# Menu-Control-Motor.net
KiCad netlist of a schematic drawn in Altium Designer
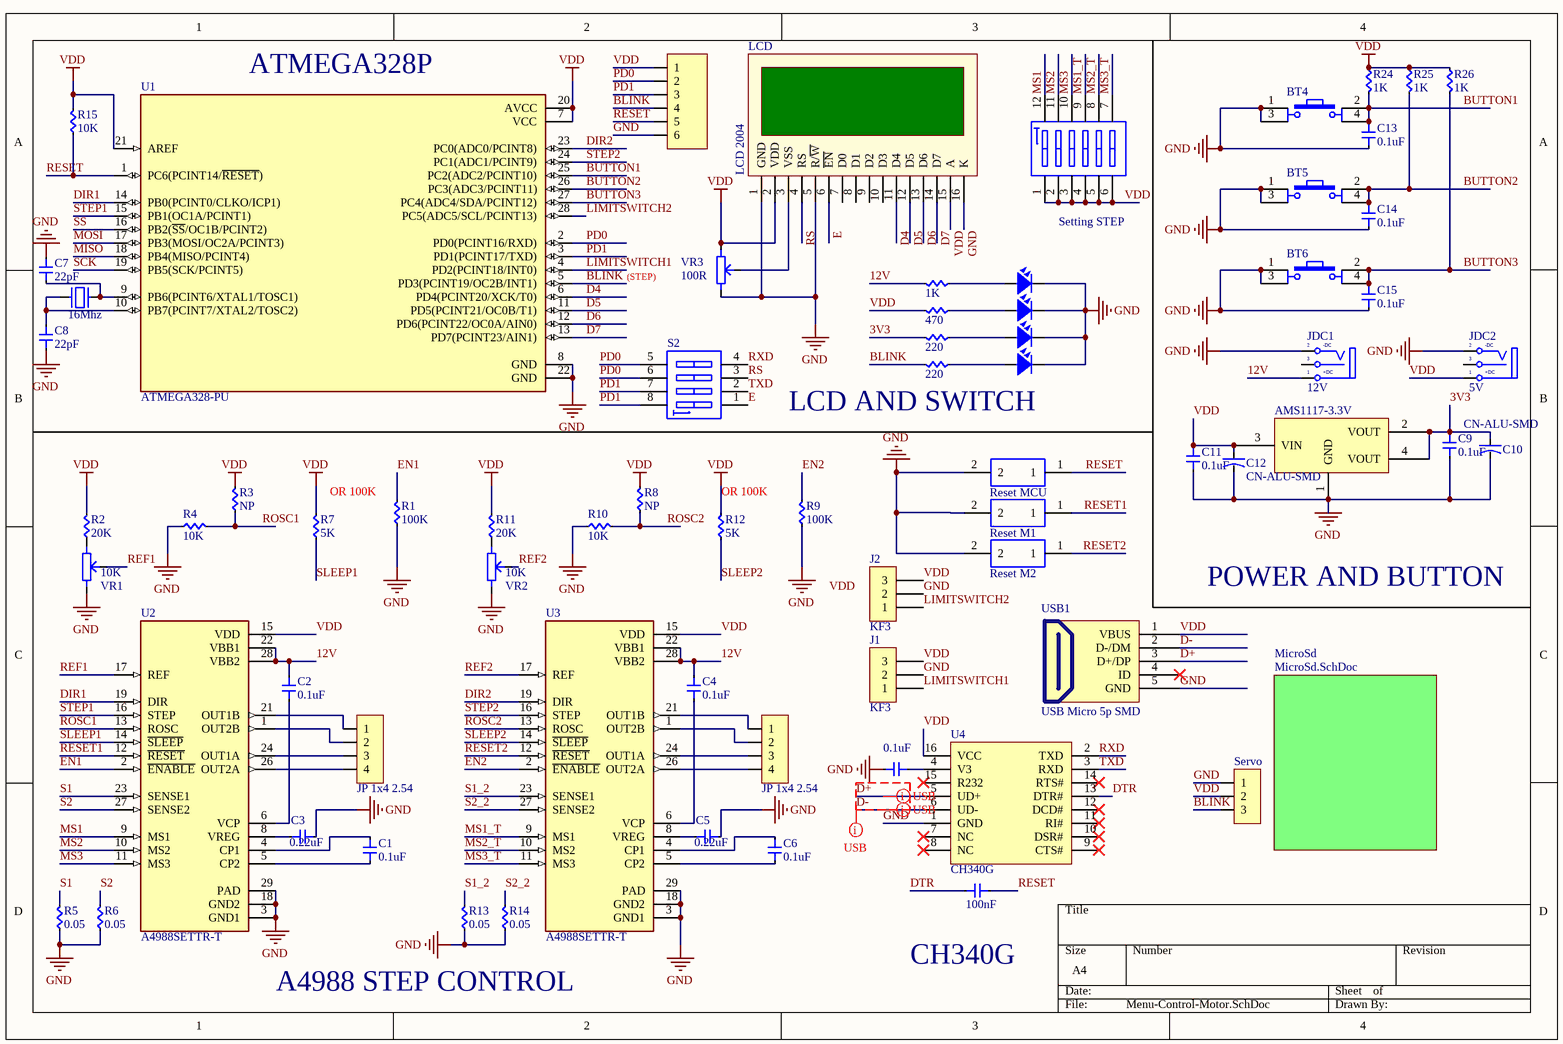
[diagram p0: Menu-Control-Motor.SchDoc]

(export (version "E")
  (design (tool "Eeschema 10.0.6"))
  (components
    (comp (ref "AMS1117-3.3V")
      (value "AMS1117-3.3V")
      (footprint "SOT223")
      (description "Dán")
      (libsource (lib "Altium_Lib_by_KhueNguyenCreator") (part "AMS1117 SMD"))
    )
    (comp (ref "BT4")
      (value "Button 4p")
      (footprint "SMD button 4 pins 6x6")
      (libsource (lib "CMN") (part "Button 4p"))
    )
    (comp (ref "BT5")
      (value "Button 4p")
      (footprint "SMD button 4 pins 6x6")
      (libsource (lib "CMN") (part "Button 4p"))
    )
    (comp (ref "BT6")
      (value "Button 4p")
      (footprint "SMD button 4 pins 6x6")
      (libsource (lib "CMN") (part "Button 4p"))
    )
    (comp (ref "C1")
      (value "0.1uF")
      (footprint "Cap 0805")
      (description "Capacitor SMD 0805")
      (libsource (lib "Altium_Lib_by_KhueNguyenCreator") (part "Cap 0805"))
    )
    (comp (ref "C2")
      (value "0.1uF")
      (footprint "Cap 0805")
      (description "Capacitor SMD 0805")
      (libsource (lib "Altium_Lib_by_KhueNguyenCreator") (part "Cap 0805"))
    )
    (comp (ref "C3")
      (value "0.22uF")
      (footprint "Cap 0805")
      (description "Capacitor SMD 0805")
      (libsource (lib "Altium_Lib_by_KhueNguyenCreator") (part "Cap 0805"))
    )
    (comp (ref "C4")
      (value "0.1uF")
      (footprint "Cap 0805")
      (description "Capacitor SMD 0805")
      (libsource (lib "Altium_Lib_by_KhueNguyenCreator") (part "Cap 0805"))
    )
    (comp (ref "C5")
      (value "0.22uF")
      (footprint "Cap 0805")
      (description "Capacitor SMD 0805")
      (libsource (lib "Altium_Lib_by_KhueNguyenCreator") (part "Cap 0805"))
    )
    (comp (ref "C6")
      (value "0.1uF")
      (footprint "Cap 0805")
      (description "Capacitor SMD 0805")
      (libsource (lib "Altium_Lib_by_KhueNguyenCreator") (part "Cap 0805"))
    )
    (comp (ref "C7")
      (value "22pF")
      (footprint "Cap 0805")
      (description "Capacitor SMD 0805")
      (libsource (lib "Altium_Lib_by_KhueNguyenCreator") (part "Cap 0805"))
    )
    (comp (ref "C8")
      (value "22pF")
      (footprint "Cap 0805")
      (description "Capacitor SMD 0805")
      (libsource (lib "Altium_Lib_by_KhueNguyenCreator") (part "Cap 0805"))
    )
    (comp (ref "C9")
      (value "0.1uF")
      (footprint "Cap 0805")
      (description "Capacitor SMD 0805")
      (libsource (lib "Altium_Lib_by_KhueNguyenCreator") (part "Cap 0805"))
    )
    (comp (ref "C10")
      (value "CN-ALU-SMD")
      (footprint "CAP-ALU-SMD-6.3x7.7x2.2")
      (description "Polarized Capacitor (Axial)")
      (fields (field (name "PUBLISHER") "Altium Limited"))
      (libsource (lib "LIBRARY") (part "CN-ALU-SMD"))
    )
    (comp (ref "C11")
      (value "0.1uF")
      (footprint "Cap 0805")
      (description "Capacitor SMD 0805")
      (libsource (lib "Altium_Lib_by_KhueNguyenCreator") (part "Cap 0805"))
    )
    (comp (ref "C12")
      (value "CN-ALU-SMD")
      (footprint "CAP-ALU-SMD-6.3x7.7x2.2")
      (description "Polarized Capacitor (Axial)")
      (fields (field (name "PUBLISHER") "Altium Limited"))
      (libsource (lib "LIBRARY") (part "CN-ALU-SMD"))
    )
    (comp (ref "C13")
      (value "0.1uF")
      (footprint "Cap 0805")
      (description "Capacitor SMD 0805")
      (libsource (lib "Altium_Lib_by_KhueNguyenCreator") (part "Cap 0805"))
    )
    (comp (ref "C14")
      (value "0.1uF")
      (footprint "Cap 0805")
      (description "Capacitor SMD 0805")
      (libsource (lib "Altium_Lib_by_KhueNguyenCreator") (part "Cap 0805"))
    )
    (comp (ref "C15")
      (value "0.1uF")
      (footprint "Cap 0805")
      (description "Capacitor SMD 0805")
      (libsource (lib "Altium_Lib_by_KhueNguyenCreator") (part "Cap 0805"))
    )
    (comp (ref "C16")
      (value "0.1uF")
      (footprint "Cap 0805")
      (description "Capacitor SMD 0805")
      (libsource (lib "Altium_Lib_by_KhueNguyenCreator") (part "Cap 0805"))
    )
    (comp (ref "C17")
      (value "100nF")
      (footprint "Cap 0805")
      (description "Capacitor SMD 0805")
      (libsource (lib "Altium_Lib_by_KhueNguyenCreator") (part "Cap 0805"))
    )
    (comp (ref "DEBUG")
      (value "CHECK")
      (footprint "JP 1x6 DT")
      (description "Cắm")
      (libsource (lib "Altium_Lib_by_KhueNguyenCreator") (part "JP 1x6 2.54 Duc Thang"))
    )
    (comp (ref "J1")
      (value "KF3")
      (footprint "KF3-5.08")
      (fields
        (field (name "MANUFACTURER") "Würth Elektronik eiSos GmbH")
        (field (name "PARTNO") "691103110003")
        (field (name "CREATED BY") "Karrer Zheng")
      )
      (libsource (lib "LIBRARY") (part "KF3"))
    )
    (comp (ref "J2")
      (value "KF3")
      (footprint "KF3-5.08")
      (fields
        (field (name "MANUFACTURER") "Würth Elektronik eiSos GmbH")
        (field (name "PARTNO") "691103110003")
        (field (name "CREATED BY") "Karrer Zheng")
      )
      (libsource (lib "LIBRARY") (part "KF3"))
    )
    (comp (ref "JDC1")
      (value "12V")
      (footprint "DC0")
      (description "Jac DC input")
      (libsource (lib "LIBRARY") (part "DCIN"))
    )
    (comp (ref "JDC2")
      (value "5V")
      (footprint "DC0")
      (description "Jac DC input")
      (libsource (lib "LIBRARY") (part "DCIN"))
    )
    (comp (ref "JP2")
      (value "JP 1x4 2.54")
      (footprint "JP 1x4 DT")
      (description "Cắm")
      (libsource (lib "Altium_Lib_by_KhueNguyenCreator") (part "JP 1x4 2.54 Duc Thang"))
    )
    (comp (ref "JP3")
      (value "JP 1x4 2.54")
      (footprint "JP 1x4 DT")
      (description "Cắm")
      (libsource (lib "Altium_Lib_by_KhueNguyenCreator") (part "JP 1x4 2.54 Duc Thang"))
    )
    (comp (ref "LCD")
      (value "LCD 2004")
      (footprint "LCD_LCD-20X4B")
      (description "LCD 2004 5V Xanh Dương")
      (libsource (lib "Altium_Lib_by_KhueNguyenCreator") (part "LCD 2004 5V"))
    )
    (comp (ref "LED1") (value "LED") (footprint "LED-0805-Blue") (libsource (lib "LIBRARY") (part "LED SMD")))
    (comp (ref "LED2") (value "LED") (footprint "LED-0805-Blue") (libsource (lib "LIBRARY") (part "LED SMD")))
    (comp (ref "LED3") (value "LED") (footprint "LED-0805-Blue") (libsource (lib "LIBRARY") (part "LED SMD")))
    (comp (ref "LED4") (value "LED") (footprint "LED-0805-Blue") (libsource (lib "LIBRARY") (part "LED SMD")))
    (comp (ref "R1")
      (value "100K")
      (footprint "RES 0805")
      (description "RES SMD 0805")
      (fields
        (field (name "MANUFACTURER") "Vishay Dale")
        (field (name "MANUFACTURER PART NUMBER") "CRCW040210K0FKED")
      )
      (libsource (lib "Altium_Lib_by_KhueNguyenCreator") (part "RES 0805"))
    )
    (comp (ref "R2")
      (value "20K")
      (footprint "RES 0805")
      (description "RES SMD 0805")
      (fields
        (field (name "MANUFACTURER") "Vishay Dale")
        (field (name "MANUFACTURER PART NUMBER") "CRCW040210K0FKED")
      )
      (libsource (lib "Altium_Lib_by_KhueNguyenCreator") (part "RES 0805"))
    )
    (comp (ref "R3")
      (value "NP")
      (footprint "RES 0805")
      (description "RES SMD 0805")
      (fields
        (field (name "MANUFACTURER") "Vishay Dale")
        (field (name "MANUFACTURER PART NUMBER") "CRCW040210K0FKED")
      )
      (libsource (lib "Altium_Lib_by_KhueNguyenCreator") (part "RES 0805"))
    )
    (comp (ref "R4")
      (value "10K")
      (footprint "RES 0805")
      (description "RES SMD 0805")
      (fields
        (field (name "MANUFACTURER") "Vishay Dale")
        (field (name "MANUFACTURER PART NUMBER") "CRCW040210K0FKED")
      )
      (libsource (lib "Altium_Lib_by_KhueNguyenCreator") (part "RES 0805"))
    )
    (comp (ref "R5")
      (value "0.05")
      (footprint "RES 0805")
      (description "RES SMD 0805")
      (fields
        (field (name "MANUFACTURER") "Vishay Dale")
        (field (name "MANUFACTURER PART NUMBER") "CRCW040210K0FKED")
      )
      (libsource (lib "Altium_Lib_by_KhueNguyenCreator") (part "RES 0805"))
    )
    (comp (ref "R6")
      (value "0.05")
      (footprint "RES 0805")
      (description "RES SMD 0805")
      (fields
        (field (name "MANUFACTURER") "Vishay Dale")
        (field (name "MANUFACTURER PART NUMBER") "CRCW040210K0FKED")
      )
      (libsource (lib "Altium_Lib_by_KhueNguyenCreator") (part "RES 0805"))
    )
    (comp (ref "R7")
      (value "5K")
      (footprint "RES 0805")
      (description "RES SMD 0805")
      (fields
        (field (name "MANUFACTURER") "Vishay Dale")
        (field (name "MANUFACTURER PART NUMBER") "CRCW040210K0FKED")
      )
      (libsource (lib "Altium_Lib_by_KhueNguyenCreator") (part "RES 0805"))
    )
    (comp (ref "R8")
      (value "NP")
      (footprint "RES 0805")
      (description "RES SMD 0805")
      (fields
        (field (name "MANUFACTURER") "Vishay Dale")
        (field (name "MANUFACTURER PART NUMBER") "CRCW040210K0FKED")
      )
      (libsource (lib "Altium_Lib_by_KhueNguyenCreator") (part "RES 0805"))
    )
    (comp (ref "R9")
      (value "100K")
      (footprint "RES 0805")
      (description "RES SMD 0805")
      (fields
        (field (name "MANUFACTURER") "Vishay Dale")
        (field (name "MANUFACTURER PART NUMBER") "CRCW040210K0FKED")
      )
      (libsource (lib "Altium_Lib_by_KhueNguyenCreator") (part "RES 0805"))
    )
    (comp (ref "R10")
      (value "10K")
      (footprint "RES 0805")
      (description "RES SMD 0805")
      (fields
        (field (name "MANUFACTURER") "Vishay Dale")
        (field (name "MANUFACTURER PART NUMBER") "CRCW040210K0FKED")
      )
      (libsource (lib "Altium_Lib_by_KhueNguyenCreator") (part "RES 0805"))
    )
    (comp (ref "R11")
      (value "20K")
      (footprint "RES 0805")
      (description "RES SMD 0805")
      (fields
        (field (name "MANUFACTURER") "Vishay Dale")
        (field (name "MANUFACTURER PART NUMBER") "CRCW040210K0FKED")
      )
      (libsource (lib "Altium_Lib_by_KhueNguyenCreator") (part "RES 0805"))
    )
    (comp (ref "R12")
      (value "5K")
      (footprint "RES 0805")
      (description "RES SMD 0805")
      (fields
        (field (name "MANUFACTURER") "Vishay Dale")
        (field (name "MANUFACTURER PART NUMBER") "CRCW040210K0FKED")
      )
      (libsource (lib "Altium_Lib_by_KhueNguyenCreator") (part "RES 0805"))
    )
    (comp (ref "R13")
      (value "0.05")
      (footprint "RES 0805")
      (description "RES SMD 0805")
      (fields
        (field (name "MANUFACTURER") "Vishay Dale")
        (field (name "MANUFACTURER PART NUMBER") "CRCW040210K0FKED")
      )
      (libsource (lib "Altium_Lib_by_KhueNguyenCreator") (part "RES 0805"))
    )
    (comp (ref "R14")
      (value "0.05")
      (footprint "RES 0805")
      (description "RES SMD 0805")
      (fields
        (field (name "MANUFACTURER") "Vishay Dale")
        (field (name "MANUFACTURER PART NUMBER") "CRCW040210K0FKED")
      )
      (libsource (lib "Altium_Lib_by_KhueNguyenCreator") (part "RES 0805"))
    )
    (comp (ref "R15")
      (value "10K")
      (footprint "RES 0805")
      (description "RES SMD 0805")
      (fields
        (field (name "MANUFACTURER") "Vishay Dale")
        (field (name "MANUFACTURER PART NUMBER") "CRCW040210K0FKED")
      )
      (libsource (lib "Altium_Lib_by_KhueNguyenCreator") (part "RES 0805"))
    )
    (comp (ref "R16")
      (value "1K")
      (footprint "RES 0805")
      (description "RES SMD 0805")
      (fields
        (field (name "MANUFACTURER") "Vishay Dale")
        (field (name "MANUFACTURER PART NUMBER") "CRCW040210K0FKED")
      )
      (libsource (lib "Altium_Lib_by_KhueNguyenCreator") (part "RES 0805"))
    )
    (comp (ref "R17")
      (value "470")
      (footprint "RES 0805")
      (description "RES SMD 0805")
      (fields
        (field (name "MANUFACTURER") "Vishay Dale")
        (field (name "MANUFACTURER PART NUMBER") "CRCW040210K0FKED")
      )
      (libsource (lib "Altium_Lib_by_KhueNguyenCreator") (part "RES 0805"))
    )
    (comp (ref "R21")
      (value "220")
      (footprint "RES 0805")
      (description "RES SMD 0805")
      (fields
        (field (name "MANUFACTURER") "Vishay Dale")
        (field (name "MANUFACTURER PART NUMBER") "CRCW040210K0FKED")
      )
      (libsource (lib "Altium_Lib_by_KhueNguyenCreator") (part "RES 0805"))
    )
    (comp (ref "R24")
      (value "1K")
      (footprint "RES 0805")
      (description "RES SMD 0805")
      (fields
        (field (name "MANUFACTURER") "Vishay Dale")
        (field (name "MANUFACTURER PART NUMBER") "CRCW040210K0FKED")
      )
      (libsource (lib "Altium_Lib_by_KhueNguyenCreator") (part "RES 0805"))
    )
    (comp (ref "R25")
      (value "1K")
      (footprint "RES 0805")
      (description "RES SMD 0805")
      (fields
        (field (name "MANUFACTURER") "Vishay Dale")
        (field (name "MANUFACTURER PART NUMBER") "CRCW040210K0FKED")
      )
      (libsource (lib "Altium_Lib_by_KhueNguyenCreator") (part "RES 0805"))
    )
    (comp (ref "R26")
      (value "1K")
      (footprint "RES 0805")
      (description "RES SMD 0805")
      (fields
        (field (name "MANUFACTURER") "Vishay Dale")
        (field (name "MANUFACTURER PART NUMBER") "CRCW040210K0FKED")
      )
      (libsource (lib "Altium_Lib_by_KhueNguyenCreator") (part "RES 0805"))
    )
    (comp (ref "R27")
      (value "220")
      (footprint "RES 0805")
      (description "RES SMD 0805")
      (fields
        (field (name "MANUFACTURER") "Vishay Dale")
        (field (name "MANUFACTURER PART NUMBER") "CRCW040210K0FKED")
      )
      (libsource (lib "Altium_Lib_by_KhueNguyenCreator") (part "RES 0805"))
    )
    (comp (ref "Reset M1")
      (value "Component_1")
      (footprint "PCBComponent_1")
      (libsource (lib "Button_SMD") (part "Component_1"))
    )
    (comp (ref "Reset M2")
      (value "Component_1")
      (footprint "PCBComponent_1")
      (libsource (lib "Button_SMD") (part "Component_1"))
    )
    (comp (ref "Reset MCU")
      (value "Component_1")
      (footprint "PCBComponent_1")
      (libsource (lib "Button_SMD") (part "Component_1"))
    )
    (comp (ref "S2")
      (value "~")
      (footprint "SW-DIP4")
      (description "WS-DITV 2.54 mm small compact THT flat actuator with top tape")
      (fields
        (field (name "MANUFACTURER") "Wurth Elektronik")
        (field (name "PART NO.") "418127160904")
        (field (name "CREATED BY") "Baojun Chen")
      )
      (libsource (lib "LIBRARY") (part "SWDIP4"))
    )
    (comp (ref "Servo")
      (value "JP 1x3 2.54")
      (footprint "JP 1x3 DT")
      (description "Cắm")
      (libsource (lib "Altium_Lib_by_KhueNguyenCreator") (part "JP 1x3 2.54 Duc Thang"))
    )
    (comp (ref "Setting STEP")
      (value "~")
      (footprint "SW-DIP6")
      (description "WS-DITV 2.54 mm small compact THT flat actuator with top tape")
      (fields
        (field (name "MANUFACTURER") "Wurth Elektronik")
        (field (name "PART NO.") "418127160906")
        (field (name "CREATED BY") "Baojun Chen")
      )
      (libsource (lib "LIBRARY") (part "SWDIP6"))
    )
    (comp (ref "U1")
      (value "ATMEGA328-PU")
      (footprint "DIP787W46P254L3467H508Q28")
      (description "AVR AVRÂ® ATmega Microcontroller IC 8-Bit 20MHz 32KB (16K x 16) FLASH 28-PDIP")
      (fields (field (name "MF") "Microchip"))
      (libsource (lib "ATMEGA328-PU") (part "ATMEGA328-PU"))
    )
    (comp (ref "U2")
      (value "A4988SETTR-T")
      (footprint "QFN50P500X500X90-29N")
      (description "Bipolar Motor Driver DMOS Logic 28-QFN (5x5)")
      (fields (field (name "MF") "Allegro") (field (name "DIGI-KEY_PART_NUMBER") "620-1343-1-ND"))
      (libsource (lib "A4988SETTR-T") (part "A4988SETTR-T"))
    )
    (comp (ref "U3")
      (value "A4988SETTR-T")
      (footprint "QFN50P500X500X90-29N")
      (description "Bipolar Motor Driver DMOS Logic 28-QFN (5x5)")
      (fields (field (name "MF") "Allegro") (field (name "DIGI-KEY_PART_NUMBER") "620-1343-1-ND"))
      (libsource (lib "A4988SETTR-T") (part "A4988SETTR-T"))
    )
    (comp (ref "U4")
      (value "CH340G")
      (footprint "SOIC16_50_284_25X90_SMT")
      (description "USB Bridge, USB to UART USB 2.0 UART Interface")
      (fields (field (name "MANUFACTURER") "Olimex") (field (name "MANUFACTURER PART NUMBER") "CH340C"))
      (libsource (lib "Altium_Lib_by_KhueNguyenCreator") (part "CH340C"))
    )
    (comp (ref "USB1")
      (value "USB Micro 5p SMD")
      (footprint "USB Micro 5p SMD")
      (description "USB Type B")
      (libsource (lib "Altium_Lib_by_KhueNguyenCreator") (part "USB Micro 5p SMD"))
    )
    (comp (ref "VR1")
      (value "10K")
      (footprint "Bien Tro Tam Giac Dung")
      (description "Cắm")
      (libsource (lib "Altium_Lib_by_KhueNguyenCreator") (part "Bien tro tam giac 10K Dung"))
    )
    (comp (ref "VR2")
      (value "10K")
      (footprint "Bien Tro Tam Giac Dung")
      (description "Cắm")
      (libsource (lib "Altium_Lib_by_KhueNguyenCreator") (part "Bien tro tam giac 10K Dung"))
    )
    (comp (ref "VR3")
      (value "100R")
      (footprint "Bien Tro Tam Giac Dung")
      (description "Cắm")
      (libsource (lib "Altium_Lib_by_KhueNguyenCreator") (part "Bien tro tam giac 100R Dung"))
    )
    (comp (ref "Y1")
      (value "16Mhz")
      (footprint "Thach Anh 2 chan cam")
      (description "Crystal For all Crystal 2pin.")
      (libsource (lib "Altium_Lib_by_KhueNguyenCreator") (part "Thach Anh 2 chan Cam"))
    )
  )
  (nets
    (net (code "1") (name "/3V3") (class "Default")
      (node (ref "AMS1117-3.3V") (pin "2") (pinfunction "VOUT_2") (pintype "passive"))
      (node (ref "AMS1117-3.3V") (pin "4") (pinfunction "VOUT_4") (pintype "passive"))
      (node (ref "C10") (pin "1") (pinfunction "1_1") (pintype "passive"))
      (node (ref "C9") (pin "1") (pinfunction "1_1") (pintype "passive"))
      (node (ref "R21") (pin "2") (pinfunction "2_2") (pintype "passive"))
    )
    (net (code "2") (name "/12V") (class "Default")
      (node (ref "C2") (pin "1") (pinfunction "1_1") (pintype "passive"))
      (node (ref "C4") (pin "1") (pinfunction "1_1") (pintype "passive"))
      (node (ref "JDC1") (pin "1") (pinfunction "T_1") (pintype "passive"))
      (node (ref "R16") (pin "2") (pinfunction "2_2") (pintype "passive"))
      (node (ref "U2") (pin "22") (pinfunction "VBB1_22") (pintype "power_in"))
      (node (ref "U2") (pin "28") (pinfunction "VBB2_28") (pintype "power_in"))
      (node (ref "U3") (pin "22") (pinfunction "VBB1_22") (pintype "power_in"))
      (node (ref "U3") (pin "28") (pinfunction "VBB2_28") (pintype "power_in"))
    )
    (net (code "3") (name "/BLINK") (class "Default")
      (node (ref "DEBUG") (pin "4") (pinfunction "4_4") (pintype "passive"))
      (node (ref "R27") (pin "2") (pinfunction "2_2") (pintype "passive"))
      (node (ref "Servo") (pin "3") (pinfunction "3_3") (pintype "passive"))
      (node (ref "U1") (pin "5") (pinfunction "PD3(PCINT19/OC2B/INT1)_5") (pintype "bidirectional"))
    )
    (net (code "4") (name "/BUTTON1") (class "Default")
      (node (ref "BT4") (pin "2") (pintype "passive"))
      (node (ref "BT4") (pin "4") (pintype "passive"))
      (node (ref "C13") (pin "1") (pinfunction "1_1") (pintype "passive"))
      (node (ref "R24") (pin "2") (pinfunction "2_2") (pintype "passive"))
      (node (ref "U1") (pin "25") (pinfunction "PC2(ADC2/PCINT10)_25") (pintype "bidirectional"))
    )
    (net (code "5") (name "/BUTTON2") (class "Default")
      (node (ref "BT5") (pin "2") (pintype "passive"))
      (node (ref "BT5") (pin "4") (pintype "passive"))
      (node (ref "C14") (pin "1") (pinfunction "1_1") (pintype "passive"))
      (node (ref "R25") (pin "2") (pinfunction "2_2") (pintype "passive"))
      (node (ref "U1") (pin "26") (pinfunction "PC3(ADC3/PCINT11)_26") (pintype "bidirectional"))
    )
    (net (code "6") (name "/BUTTON3") (class "Default")
      (node (ref "BT6") (pin "2") (pintype "passive"))
      (node (ref "BT6") (pin "4") (pintype "passive"))
      (node (ref "C15") (pin "1") (pinfunction "1_1") (pintype "passive"))
      (node (ref "R26") (pin "2") (pinfunction "2_2") (pintype "passive"))
      (node (ref "U1") (pin "27") (pinfunction "PC4(ADC4/SDA/PCINT12)_27") (pintype "bidirectional"))
    )
    (net (code "7") (name "/D+") (class "Default")
      (node (ref "U4") (pin "5") (pinfunction "UD+_5") (pintype "passive"))
      (node (ref "USB1") (pin "3") (pinfunction "D+/DP_3") (pintype "passive"))
    )
    (net (code "8") (name "/D-") (class "Default")
      (node (ref "U4") (pin "6") (pinfunction "UD-_6") (pintype "passive"))
      (node (ref "USB1") (pin "2") (pinfunction "D-/DM_2") (pintype "passive"))
    )
    (net (code "9") (name "/D4") (class "Default")
      (node (ref "LCD") (pin "11") (pinfunction "D4_11") (pintype "passive"))
      (node (ref "U1") (pin "6") (pinfunction "PD4(PCINT20/XCK/T0)_6") (pintype "bidirectional"))
    )
    (net (code "10") (name "/D5") (class "Default")
      (node (ref "LCD") (pin "12") (pinfunction "D5_12") (pintype "passive"))
      (node (ref "U1") (pin "11") (pinfunction "PD5(PCINT21/OC0B/T1)_11") (pintype "bidirectional"))
    )
    (net (code "11") (name "/D6") (class "Default")
      (node (ref "LCD") (pin "13") (pinfunction "D6_13") (pintype "passive"))
      (node (ref "U1") (pin "12") (pinfunction "PD6(PCINT22/OC0A/AIN0)_12") (pintype "bidirectional"))
    )
    (net (code "12") (name "/D7") (class "Default")
      (node (ref "LCD") (pin "14") (pinfunction "D7_14") (pintype "passive"))
      (node (ref "U1") (pin "13") (pinfunction "PD7(PCINT23/AIN1)_13") (pintype "bidirectional"))
    )
    (net (code "13") (name "/DIR1") (class "Default")
      (node (ref "U1") (pin "14") (pinfunction "PB0(PCINT0/CLKO/ICP1)_14") (pintype "bidirectional"))
      (node (ref "U2") (pin "19") (pinfunction "DIR_19") (pintype "input"))
    )
    (net (code "14") (name "/DIR2") (class "Default")
      (node (ref "U1") (pin "23") (pinfunction "PC0(ADC0/PCINT8)_23") (pintype "bidirectional"))
      (node (ref "U3") (pin "19") (pinfunction "DIR_19") (pintype "input"))
    )
    (net (code "15") (name "/DTR") (class "Default")
      (node (ref "C17") (pin "1") (pinfunction "1_1") (pintype "passive"))
      (node (ref "U4") (pin "13") (pinfunction "DTR#_13") (pintype "passive"))
    )
    (net (code "16") (name "/E") (class "Default")
      (node (ref "LCD") (pin "6") (pinfunction "~{EN}_6") (pintype "passive"))
      (node (ref "S2") (pin "1") (pinfunction "1_1") (pintype "passive"))
    )
    (net (code "17") (name "/EN1") (class "Default")
      (node (ref "R1") (pin "2") (pinfunction "2_2") (pintype "passive"))
      (node (ref "U2") (pin "2") (pinfunction "~{ENABLE}_2") (pintype "input"))
    )
    (net (code "18") (name "/EN2") (class "Default")
      (node (ref "R9") (pin "2") (pinfunction "2_2") (pintype "passive"))
      (node (ref "U3") (pin "2") (pinfunction "~{ENABLE}_2") (pintype "input"))
    )
    (net (code "19") (name "/LIMITSWITCH1") (class "Default")
      (node (ref "J1") (pin "1") (pinfunction "1_1") (pintype "passive"))
      (node (ref "U1") (pin "4") (pinfunction "PD2(PCINT18/INT0)_4") (pintype "bidirectional"))
    )
    (net (code "20") (name "/LIMITSWITCH2") (class "Default")
      (node (ref "J2") (pin "1") (pinfunction "1_1") (pintype "passive"))
      (node (ref "U1") (pin "28") (pinfunction "PC5(ADC5/SCL/PCINT13)_28") (pintype "bidirectional"))
    )
    (net (code "21") (name "/MISO") (class "Default")
      (node (ref "U1") (pin "18") (pinfunction "PB4(MISO/PCINT4)_18") (pintype "bidirectional"))
    )
    (net (code "22") (name "/MOSI") (class "Default")
      (node (ref "U1") (pin "17") (pinfunction "PB3(MOSI/OC2A/PCINT3)_17") (pintype "bidirectional"))
    )
    (net (code "23") (name "/MS1") (class "Default")
      (node (ref "Setting STEP") (pin "12") (pinfunction "12_12") (pintype "passive"))
      (node (ref "U2") (pin "9") (pinfunction "MS1_9") (pintype "input"))
    )
    (net (code "24") (name "/MS1_T") (class "Default")
      (node (ref "Setting STEP") (pin "9") (pinfunction "9_9") (pintype "passive"))
      (node (ref "U3") (pin "9") (pinfunction "MS1_9") (pintype "input"))
    )
    (net (code "25") (name "/MS2") (class "Default")
      (node (ref "Setting STEP") (pin "11") (pinfunction "11_11") (pintype "passive"))
      (node (ref "U2") (pin "10") (pinfunction "MS2_10") (pintype "input"))
    )
    (net (code "26") (name "/MS2_T") (class "Default")
      (node (ref "Setting STEP") (pin "8") (pinfunction "8_8") (pintype "passive"))
      (node (ref "U3") (pin "10") (pinfunction "MS2_10") (pintype "input"))
    )
    (net (code "27") (name "/MS3") (class "Default")
      (node (ref "Setting STEP") (pin "10") (pinfunction "10_10") (pintype "passive"))
      (node (ref "U2") (pin "11") (pinfunction "MS3_11") (pintype "input"))
    )
    (net (code "28") (name "/MS3_T") (class "Default")
      (node (ref "Setting STEP") (pin "7") (pinfunction "7_7") (pintype "passive"))
      (node (ref "U3") (pin "11") (pinfunction "MS3_11") (pintype "input"))
    )
    (net (code "29") (name "/PD0") (class "Default")
      (node (ref "DEBUG") (pin "2") (pinfunction "2_2") (pintype "passive"))
      (node (ref "S2") (pin "5") (pinfunction "5_5") (pintype "passive"))
      (node (ref "S2") (pin "6") (pinfunction "6_6") (pintype "passive"))
      (node (ref "U1") (pin "2") (pinfunction "PD0(PCINT16/RXD)_2") (pintype "bidirectional"))
    )
    (net (code "30") (name "/PD1") (class "Default")
      (node (ref "DEBUG") (pin "3") (pinfunction "3_3") (pintype "passive"))
      (node (ref "S2") (pin "7") (pinfunction "7_7") (pintype "passive"))
      (node (ref "S2") (pin "8") (pinfunction "8_8") (pintype "passive"))
      (node (ref "U1") (pin "3") (pinfunction "PD1(PCINT17/TXD)_3") (pintype "bidirectional"))
    )
    (net (code "31") (name "/REF1") (class "Default")
      (node (ref "U2") (pin "17") (pinfunction "REF_17") (pintype "input"))
      (node (ref "VR1") (pin "2") (pinfunction "2_2") (pintype "passive"))
    )
    (net (code "32") (name "/REF2") (class "Default")
      (node (ref "U3") (pin "17") (pinfunction "REF_17") (pintype "input"))
      (node (ref "VR2") (pin "2") (pinfunction "2_2") (pintype "passive"))
    )
    (net (code "33") (name "/RESET") (class "Default")
      (node (ref "C17") (pin "2") (pinfunction "2_2") (pintype "passive"))
      (node (ref "DEBUG") (pin "5") (pinfunction "5_5") (pintype "passive"))
      (node (ref "R15") (pin "1") (pinfunction "1_1") (pintype "passive"))
      (node (ref "Reset MCU") (pin "1") (pinfunction "1_1") (pintype "passive"))
      (node (ref "U1") (pin "1") (pinfunction "PC6(PCINT14/~{RESET})_1") (pintype "bidirectional"))
    )
    (net (code "34") (name "/RESET1") (class "Default")
      (node (ref "Reset M1") (pin "1") (pinfunction "1_1") (pintype "passive"))
      (node (ref "U2") (pin "12") (pinfunction "~{RESET}_12") (pintype "input"))
    )
    (net (code "35") (name "/RESET2") (class "Default")
      (node (ref "Reset M2") (pin "1") (pinfunction "1_1") (pintype "passive"))
      (node (ref "U3") (pin "12") (pinfunction "~{RESET}_12") (pintype "input"))
    )
    (net (code "36") (name "/ROSC1") (class "Default")
      (node (ref "R3") (pin "1") (pinfunction "1_1") (pintype "passive"))
      (node (ref "R4") (pin "2") (pinfunction "2_2") (pintype "passive"))
      (node (ref "U2") (pin "13") (pinfunction "ROSC_13") (pintype "input"))
    )
    (net (code "37") (name "/ROSC2") (class "Default")
      (node (ref "R10") (pin "2") (pinfunction "2_2") (pintype "passive"))
      (node (ref "R8") (pin "1") (pinfunction "1_1") (pintype "passive"))
      (node (ref "U3") (pin "13") (pinfunction "ROSC_13") (pintype "input"))
    )
    (net (code "38") (name "/RS") (class "Default")
      (node (ref "LCD") (pin "4") (pinfunction "RS_4") (pintype "passive"))
      (node (ref "S2") (pin "3") (pinfunction "3_3") (pintype "passive"))
    )
    (net (code "39") (name "/RXD") (class "Default")
      (node (ref "S2") (pin "4") (pinfunction "4_4") (pintype "passive"))
      (node (ref "U4") (pin "2") (pinfunction "TXD_2") (pintype "passive"))
    )
    (net (code "40") (name "/S1") (class "Default")
      (node (ref "R5") (pin "2") (pinfunction "2_2") (pintype "passive"))
      (node (ref "U2") (pin "23") (pinfunction "SENSE1_23") (pintype "input"))
    )
    (net (code "41") (name "/S1_2") (class "Default")
      (node (ref "R13") (pin "2") (pinfunction "2_2") (pintype "passive"))
      (node (ref "U3") (pin "23") (pinfunction "SENSE1_23") (pintype "input"))
    )
    (net (code "42") (name "/S2") (class "Default")
      (node (ref "R6") (pin "2") (pinfunction "2_2") (pintype "passive"))
      (node (ref "U2") (pin "27") (pinfunction "SENSE2_27") (pintype "input"))
    )
    (net (code "43") (name "/S2_2") (class "Default")
      (node (ref "R14") (pin "2") (pinfunction "2_2") (pintype "passive"))
      (node (ref "U3") (pin "27") (pinfunction "SENSE2_27") (pintype "input"))
    )
    (net (code "44") (name "/SCK") (class "Default")
      (node (ref "U1") (pin "19") (pinfunction "PB5(SCK/PCINT5)_19") (pintype "bidirectional"))
    )
    (net (code "45") (name "/SLEEP1") (class "Default")
      (node (ref "R7") (pin "1") (pinfunction "1_1") (pintype "passive"))
      (node (ref "U2") (pin "14") (pinfunction "~{SLEEP}_14") (pintype "input"))
    )
    (net (code "46") (name "/SLEEP2") (class "Default")
      (node (ref "R12") (pin "1") (pinfunction "1_1") (pintype "passive"))
      (node (ref "U3") (pin "14") (pinfunction "~{SLEEP}_14") (pintype "input"))
    )
    (net (code "47") (name "/SS") (class "Default")
      (node (ref "U1") (pin "16") (pinfunction "PB2(~{SS}/OC1B/PCINT2)_16") (pintype "bidirectional"))
    )
    (net (code "48") (name "/STEP1") (class "Default")
      (node (ref "U1") (pin "15") (pinfunction "PB1(OC1A/PCINT1)_15") (pintype "bidirectional"))
      (node (ref "U2") (pin "16") (pinfunction "STEP_16") (pintype "input"))
    )
    (net (code "49") (name "/STEP2") (class "Default")
      (node (ref "U1") (pin "24") (pinfunction "PC1(ADC1/PCINT9)_24") (pintype "bidirectional"))
      (node (ref "U3") (pin "16") (pinfunction "STEP_16") (pintype "input"))
    )
    (net (code "50") (name "/TXD") (class "Default")
      (node (ref "S2") (pin "2") (pinfunction "2_2") (pintype "passive"))
      (node (ref "U4") (pin "3") (pinfunction "RXD_3") (pintype "passive"))
    )
    (net (code "51") (name "GND") (class "Default")
      (node (ref "AMS1117-3.3V") (pin "1") (pinfunction "GND_1") (pintype "passive"))
      (node (ref "BT4") (pin "1") (pintype "passive"))
      (node (ref "BT4") (pin "3") (pintype "passive"))
      (node (ref "BT5") (pin "1") (pintype "passive"))
      (node (ref "BT5") (pin "3") (pintype "passive"))
      (node (ref "BT6") (pin "1") (pintype "passive"))
      (node (ref "BT6") (pin "3") (pintype "passive"))
      (node (ref "C10") (pin "2") (pinfunction "2_2") (pintype "passive"))
      (node (ref "C11") (pin "2") (pinfunction "2_2") (pintype "passive"))
      (node (ref "C12") (pin "2") (pinfunction "2_2") (pintype "passive"))
      (node (ref "C13") (pin "2") (pinfunction "2_2") (pintype "passive"))
      (node (ref "C14") (pin "2") (pinfunction "2_2") (pintype "passive"))
      (node (ref "C15") (pin "2") (pinfunction "2_2") (pintype "passive"))
      (node (ref "C16") (pin "1") (pinfunction "1_1") (pintype "passive"))
      (node (ref "C3") (pin "2") (pinfunction "2_2") (pintype "passive"))
      (node (ref "C5") (pin "2") (pinfunction "2_2") (pintype "passive"))
      (node (ref "C7") (pin "2") (pinfunction "2_2") (pintype "passive"))
      (node (ref "C8") (pin "1") (pinfunction "1_1") (pintype "passive"))
      (node (ref "C9") (pin "2") (pinfunction "2_2") (pintype "passive"))
      (node (ref "DEBUG") (pin "6") (pinfunction "6_6") (pintype "passive"))
      (node (ref "J1") (pin "2") (pinfunction "2_2") (pintype "passive"))
      (node (ref "J2") (pin "2") (pinfunction "2_2") (pintype "passive"))
      (node (ref "JDC1") (pin "2") (pinfunction "TN_2") (pintype "passive"))
      (node (ref "JDC2") (pin "2") (pinfunction "TN_2") (pintype "passive"))
      (node (ref "LCD") (pin "1") (pinfunction "GND_1") (pintype "passive"))
      (node (ref "LCD") (pin "16") (pinfunction "K_16") (pintype "passive"))
      (node (ref "LCD") (pin "5") (pinfunction "R/~{W}_5") (pintype "passive"))
      (node (ref "LED1") (pin "2") (pinfunction "2_2") (pintype "passive"))
      (node (ref "LED2") (pin "2") (pinfunction "2_2") (pintype "passive"))
      (node (ref "LED3") (pin "2") (pinfunction "2_2") (pintype "passive"))
      (node (ref "LED4") (pin "2") (pinfunction "2_2") (pintype "passive"))
      (node (ref "R1") (pin "1") (pinfunction "1_1") (pintype "passive"))
      (node (ref "R10") (pin "1") (pinfunction "1_1") (pintype "passive"))
      (node (ref "R13") (pin "1") (pinfunction "1_1") (pintype "passive"))
      (node (ref "R14") (pin "1") (pinfunction "1_1") (pintype "passive"))
      (node (ref "R4") (pin "1") (pinfunction "1_1") (pintype "passive"))
      (node (ref "R5") (pin "1") (pinfunction "1_1") (pintype "passive"))
      (node (ref "R6") (pin "1") (pinfunction "1_1") (pintype "passive"))
      (node (ref "R9") (pin "1") (pinfunction "1_1") (pintype "passive"))
      (node (ref "Reset M1") (pin "2") (pinfunction "2_2") (pintype "passive"))
      (node (ref "Reset M2") (pin "2") (pinfunction "2_2") (pintype "passive"))
      (node (ref "Reset MCU") (pin "2") (pinfunction "2_2") (pintype "passive"))
      (node (ref "Servo") (pin "1") (pinfunction "1_1") (pintype "passive"))
      (node (ref "U1") (pin "22") (pinfunction "GND_22") (pintype "power_in"))
      (node (ref "U1") (pin "8") (pinfunction "GND_8") (pintype "power_in"))
      (node (ref "U2") (pin "18") (pinfunction "GND2_18") (pintype "passive"))
      (node (ref "U2") (pin "29") (pinfunction "PAD_29") (pintype "passive"))
      (node (ref "U2") (pin "3") (pinfunction "GND1_3") (pintype "passive"))
      (node (ref "U3") (pin "18") (pinfunction "GND2_18") (pintype "passive"))
      (node (ref "U3") (pin "29") (pinfunction "PAD_29") (pintype "passive"))
      (node (ref "U3") (pin "3") (pinfunction "GND1_3") (pintype "passive"))
      (node (ref "U4") (pin "1") (pinfunction "GND_1") (pintype "passive"))
      (node (ref "USB1") (pin "5") (pinfunction "GND_5") (pintype "passive"))
      (node (ref "VR1") (pin "3") (pinfunction "3_3") (pintype "passive"))
      (node (ref "VR2") (pin "3") (pinfunction "3_3") (pintype "passive"))
      (node (ref "VR3") (pin "3") (pinfunction "3_3") (pintype "passive"))
    )
    (net (code "52") (name "Net-(LCD-VSS)") (class "Default")
      (node (ref "LCD") (pin "3") (pinfunction "VSS_3") (pintype "passive"))
      (node (ref "VR3") (pin "2") (pinfunction "2_2") (pintype "passive"))
    )
    (net (code "53") (name "Net-(LED1-Pad1)") (class "Default")
      (node (ref "LED1") (pin "1") (pinfunction "1_1") (pintype "passive"))
      (node (ref "R16") (pin "1") (pinfunction "1_1") (pintype "passive"))
    )
    (net (code "54") (name "Net-(LED2-Pad1)") (class "Default")
      (node (ref "LED2") (pin "1") (pinfunction "1_1") (pintype "passive"))
      (node (ref "R17") (pin "1") (pinfunction "1_1") (pintype "passive"))
    )
    (net (code "55") (name "Net-(LED3-Pad1)") (class "Default")
      (node (ref "LED3") (pin "1") (pinfunction "1_1") (pintype "passive"))
      (node (ref "R21") (pin "1") (pinfunction "1_1") (pintype "passive"))
    )
    (net (code "56") (name "Net-(LED4-Pad1)") (class "Default")
      (node (ref "LED4") (pin "1") (pinfunction "1_1") (pintype "passive"))
      (node (ref "R27") (pin "1") (pinfunction "1_1") (pintype "passive"))
    )
    (net (code "57") (name "Net-(R2-Pad1)") (class "Default")
      (node (ref "R2") (pin "1") (pinfunction "1_1") (pintype "passive"))
      (node (ref "VR1") (pin "1") (pinfunction "1_1") (pintype "passive"))
    )
    (net (code "58") (name "Net-(R11-Pad1)") (class "Default")
      (node (ref "R11") (pin "1") (pinfunction "1_1") (pintype "passive"))
      (node (ref "VR2") (pin "1") (pinfunction "1_1") (pintype "passive"))
    )
    (net (code "59") (name "Net-(U1-PB6(PCINT6{slash}XTAL1{slash}TOSC1))") (class "Default")
      (node (ref "C7") (pin "1") (pinfunction "1_1") (pintype "passive"))
      (node (ref "U1") (pin "9") (pinfunction "PB6(PCINT6/XTAL1/TOSC1)_9") (pintype "bidirectional"))
      (node (ref "Y1") (pin "2") (pinfunction "2_2") (pintype "passive"))
    )
    (net (code "60") (name "Net-(U1-PB7(PCINT7{slash}XTAL2{slash}TOSC2))") (class "Default")
      (node (ref "C8") (pin "2") (pinfunction "2_2") (pintype "passive"))
      (node (ref "U1") (pin "10") (pinfunction "PB7(PCINT7/XTAL2/TOSC2)_10") (pintype "bidirectional"))
      (node (ref "Y1") (pin "1") (pinfunction "1_1") (pintype "passive"))
    )
    (net (code "61") (name "Net-(U2-CP1)") (class "Default")
      (node (ref "C1") (pin "1") (pinfunction "1_1") (pintype "passive"))
      (node (ref "U2") (pin "4") (pinfunction "CP1_4") (pintype "passive"))
    )
    (net (code "62") (name "Net-(U2-CP2)") (class "Default")
      (node (ref "C1") (pin "2") (pinfunction "2_2") (pintype "passive"))
      (node (ref "U2") (pin "5") (pinfunction "CP2_5") (pintype "passive"))
    )
    (net (code "63") (name "Net-(U2-OUT1A)") (class "Default")
      (node (ref "JP2") (pin "3") (pinfunction "3_3") (pintype "passive"))
      (node (ref "U2") (pin "24") (pinfunction "OUT1A_24") (pintype "output"))
    )
    (net (code "64") (name "Net-(U2-OUT1B)") (class "Default")
      (node (ref "JP2") (pin "1") (pinfunction "1_1") (pintype "passive"))
      (node (ref "U2") (pin "21") (pinfunction "OUT1B_21") (pintype "output"))
    )
    (net (code "65") (name "Net-(U2-OUT2A)") (class "Default")
      (node (ref "JP2") (pin "4") (pinfunction "4_4") (pintype "passive"))
      (node (ref "U2") (pin "26") (pinfunction "OUT2A_26") (pintype "output"))
    )
    (net (code "66") (name "Net-(U2-OUT2B)") (class "Default")
      (node (ref "JP2") (pin "2") (pinfunction "2_2") (pintype "passive"))
      (node (ref "U2") (pin "1") (pinfunction "OUT2B_1") (pintype "output"))
    )
    (net (code "67") (name "Net-(U2-VCP)") (class "Default")
      (node (ref "C2") (pin "2") (pinfunction "2_2") (pintype "passive"))
      (node (ref "U2") (pin "6") (pinfunction "VCP_6") (pintype "passive"))
    )
    (net (code "68") (name "Net-(U2-VREG)") (class "Default")
      (node (ref "C3") (pin "1") (pinfunction "1_1") (pintype "passive"))
      (node (ref "U2") (pin "8") (pinfunction "VREG_8") (pintype "passive"))
    )
    (net (code "69") (name "Net-(U3-CP1)") (class "Default")
      (node (ref "C6") (pin "1") (pinfunction "1_1") (pintype "passive"))
      (node (ref "U3") (pin "4") (pinfunction "CP1_4") (pintype "passive"))
    )
    (net (code "70") (name "Net-(U3-CP2)") (class "Default")
      (node (ref "C6") (pin "2") (pinfunction "2_2") (pintype "passive"))
      (node (ref "U3") (pin "5") (pinfunction "CP2_5") (pintype "passive"))
    )
    (net (code "71") (name "Net-(U3-OUT1A)") (class "Default")
      (node (ref "JP3") (pin "3") (pinfunction "3_3") (pintype "passive"))
      (node (ref "U3") (pin "24") (pinfunction "OUT1A_24") (pintype "output"))
    )
    (net (code "72") (name "Net-(U3-OUT1B)") (class "Default")
      (node (ref "JP3") (pin "1") (pinfunction "1_1") (pintype "passive"))
      (node (ref "U3") (pin "21") (pinfunction "OUT1B_21") (pintype "output"))
    )
    (net (code "73") (name "Net-(U3-OUT2A)") (class "Default")
      (node (ref "JP3") (pin "4") (pinfunction "4_4") (pintype "passive"))
      (node (ref "U3") (pin "26") (pinfunction "OUT2A_26") (pintype "output"))
    )
    (net (code "74") (name "Net-(U3-OUT2B)") (class "Default")
      (node (ref "JP3") (pin "2") (pinfunction "2_2") (pintype "passive"))
      (node (ref "U3") (pin "1") (pinfunction "OUT2B_1") (pintype "output"))
    )
    (net (code "75") (name "Net-(U3-VCP)") (class "Default")
      (node (ref "C4") (pin "2") (pinfunction "2_2") (pintype "passive"))
      (node (ref "U3") (pin "6") (pinfunction "VCP_6") (pintype "passive"))
    )
    (net (code "76") (name "Net-(U3-VREG)") (class "Default")
      (node (ref "C5") (pin "1") (pinfunction "1_1") (pintype "passive"))
      (node (ref "U3") (pin "8") (pinfunction "VREG_8") (pintype "passive"))
    )
    (net (code "77") (name "Net-(U4-V3)") (class "Default")
      (node (ref "C16") (pin "2") (pinfunction "2_2") (pintype "passive"))
      (node (ref "U4") (pin "4") (pinfunction "V3_4") (pintype "passive"))
    )
    (net (code "78") (name "VDD") (class "Default")
      (node (ref "AMS1117-3.3V") (pin "3") (pinfunction "VIN_3") (pintype "passive"))
      (node (ref "C11") (pin "1") (pinfunction "1_1") (pintype "passive"))
      (node (ref "C12") (pin "1") (pinfunction "1_1") (pintype "passive"))
      (node (ref "DEBUG") (pin "1") (pinfunction "1_1") (pintype "passive"))
      (node (ref "J1") (pin "3") (pinfunction "3_3") (pintype "passive"))
      (node (ref "J2") (pin "3") (pinfunction "3_3") (pintype "passive"))
      (node (ref "JDC2") (pin "1") (pinfunction "T_1") (pintype "passive"))
      (node (ref "LCD") (pin "15") (pinfunction "A_15") (pintype "passive"))
      (node (ref "LCD") (pin "2") (pinfunction "VDD_2") (pintype "passive"))
      (node (ref "R11") (pin "2") (pinfunction "2_2") (pintype "passive"))
      (node (ref "R12") (pin "2") (pinfunction "2_2") (pintype "passive"))
      (node (ref "R15") (pin "2") (pinfunction "2_2") (pintype "passive"))
      (node (ref "R17") (pin "2") (pinfunction "2_2") (pintype "passive"))
      (node (ref "R2") (pin "2") (pinfunction "2_2") (pintype "passive"))
      (node (ref "R24") (pin "1") (pinfunction "1_1") (pintype "passive"))
      (node (ref "R25") (pin "1") (pinfunction "1_1") (pintype "passive"))
      (node (ref "R26") (pin "1") (pinfunction "1_1") (pintype "passive"))
      (node (ref "R3") (pin "2") (pinfunction "2_2") (pintype "passive"))
      (node (ref "R7") (pin "2") (pinfunction "2_2") (pintype "passive"))
      (node (ref "R8") (pin "2") (pinfunction "2_2") (pintype "passive"))
      (node (ref "Servo") (pin "2") (pinfunction "2_2") (pintype "passive"))
      (node (ref "Setting STEP") (pin "1") (pinfunction "1_1") (pintype "passive"))
      (node (ref "Setting STEP") (pin "2") (pinfunction "2_2") (pintype "passive"))
      (node (ref "Setting STEP") (pin "3") (pinfunction "3_3") (pintype "passive"))
      (node (ref "Setting STEP") (pin "4") (pinfunction "4_4") (pintype "passive"))
      (node (ref "Setting STEP") (pin "5") (pinfunction "5_5") (pintype "passive"))
      (node (ref "Setting STEP") (pin "6") (pinfunction "6_6") (pintype "passive"))
      (node (ref "U1") (pin "20") (pinfunction "AVCC_20") (pintype "power_in"))
      (node (ref "U1") (pin "21") (pinfunction "AREF_21") (pintype "input"))
      (node (ref "U1") (pin "7") (pinfunction "VCC_7") (pintype "power_in"))
      (node (ref "U2") (pin "15") (pinfunction "VDD_15") (pintype "power_in"))
      (node (ref "U3") (pin "15") (pinfunction "VDD_15") (pintype "power_in"))
      (node (ref "U4") (pin "16") (pinfunction "VCC_16") (pintype "passive"))
      (node (ref "USB1") (pin "1") (pinfunction "VBUS_1") (pintype "passive"))
      (node (ref "VR3") (pin "1") (pinfunction "1_1") (pintype "passive"))
    )
    (net (code "79") (name "unconnected-(JDC1-S-Pad3)") (class "Default")
      (node (ref "JDC1") (pin "3") (pinfunction "S_3") (pintype "power_in"))
    )
    (net (code "80") (name "unconnected-(JDC2-S-Pad3)") (class "Default")
      (node (ref "JDC2") (pin "3") (pinfunction "S_3") (pintype "power_in"))
    )
    (net (code "81") (name "unconnected-(LCD-D0-Pad7)") (class "Default")
      (node (ref "LCD") (pin "7") (pinfunction "D0_7") (pintype "passive"))
    )
    (net (code "82") (name "unconnected-(LCD-D1-Pad8)") (class "Default")
      (node (ref "LCD") (pin "8") (pinfunction "D1_8") (pintype "passive"))
    )
    (net (code "83") (name "unconnected-(LCD-D2-Pad9)") (class "Default")
      (node (ref "LCD") (pin "9") (pinfunction "D2_9") (pintype "passive"))
    )
    (net (code "84") (name "unconnected-(LCD-D3-Pad10)") (class "Default")
      (node (ref "LCD") (pin "10") (pinfunction "D3_10") (pintype "passive"))
    )
    (net (code "85") (name "unconnected-(U4-CTS#-Pad9)") (class "Default")
      (node (ref "U4") (pin "9") (pinfunction "CTS#_9") (pintype "passive+no_connect"))
    )
    (net (code "86") (name "unconnected-(U4-DCD#-Pad12)") (class "Default")
      (node (ref "U4") (pin "12") (pinfunction "DCD#_12") (pintype "passive+no_connect"))
    )
    (net (code "87") (name "unconnected-(U4-DSR#-Pad10)") (class "Default")
      (node (ref "U4") (pin "10") (pinfunction "DSR#_10") (pintype "passive+no_connect"))
    )
    (net (code "88") (name "unconnected-(U4-NC-Pad7)") (class "Default")
      (node (ref "U4") (pin "7") (pinfunction "NC_7") (pintype "passive+no_connect"))
    )
    (net (code "89") (name "unconnected-(U4-NC-Pad8)") (class "Default")
      (node (ref "U4") (pin "8") (pinfunction "NC_8") (pintype "passive+no_connect"))
    )
    (net (code "90") (name "unconnected-(U4-R232-Pad15)") (class "Default")
      (node (ref "U4") (pin "15") (pinfunction "R232_15") (pintype "passive+no_connect"))
    )
    (net (code "91") (name "unconnected-(U4-RI#-Pad11)") (class "Default")
      (node (ref "U4") (pin "11") (pinfunction "RI#_11") (pintype "passive+no_connect"))
    )
    (net (code "92") (name "unconnected-(U4-RTS#-Pad14)") (class "Default")
      (node (ref "U4") (pin "14") (pinfunction "RTS#_14") (pintype "passive+no_connect"))
    )
    (net (code "93") (name "unconnected-(USB1-ID-Pad4)") (class "Default")
      (node (ref "USB1") (pin "4") (pinfunction "ID_4") (pintype "passive+no_connect"))
    )
  )
)
